# TC_board.net
KiCad netlist of a schematic drawn in EAGLE
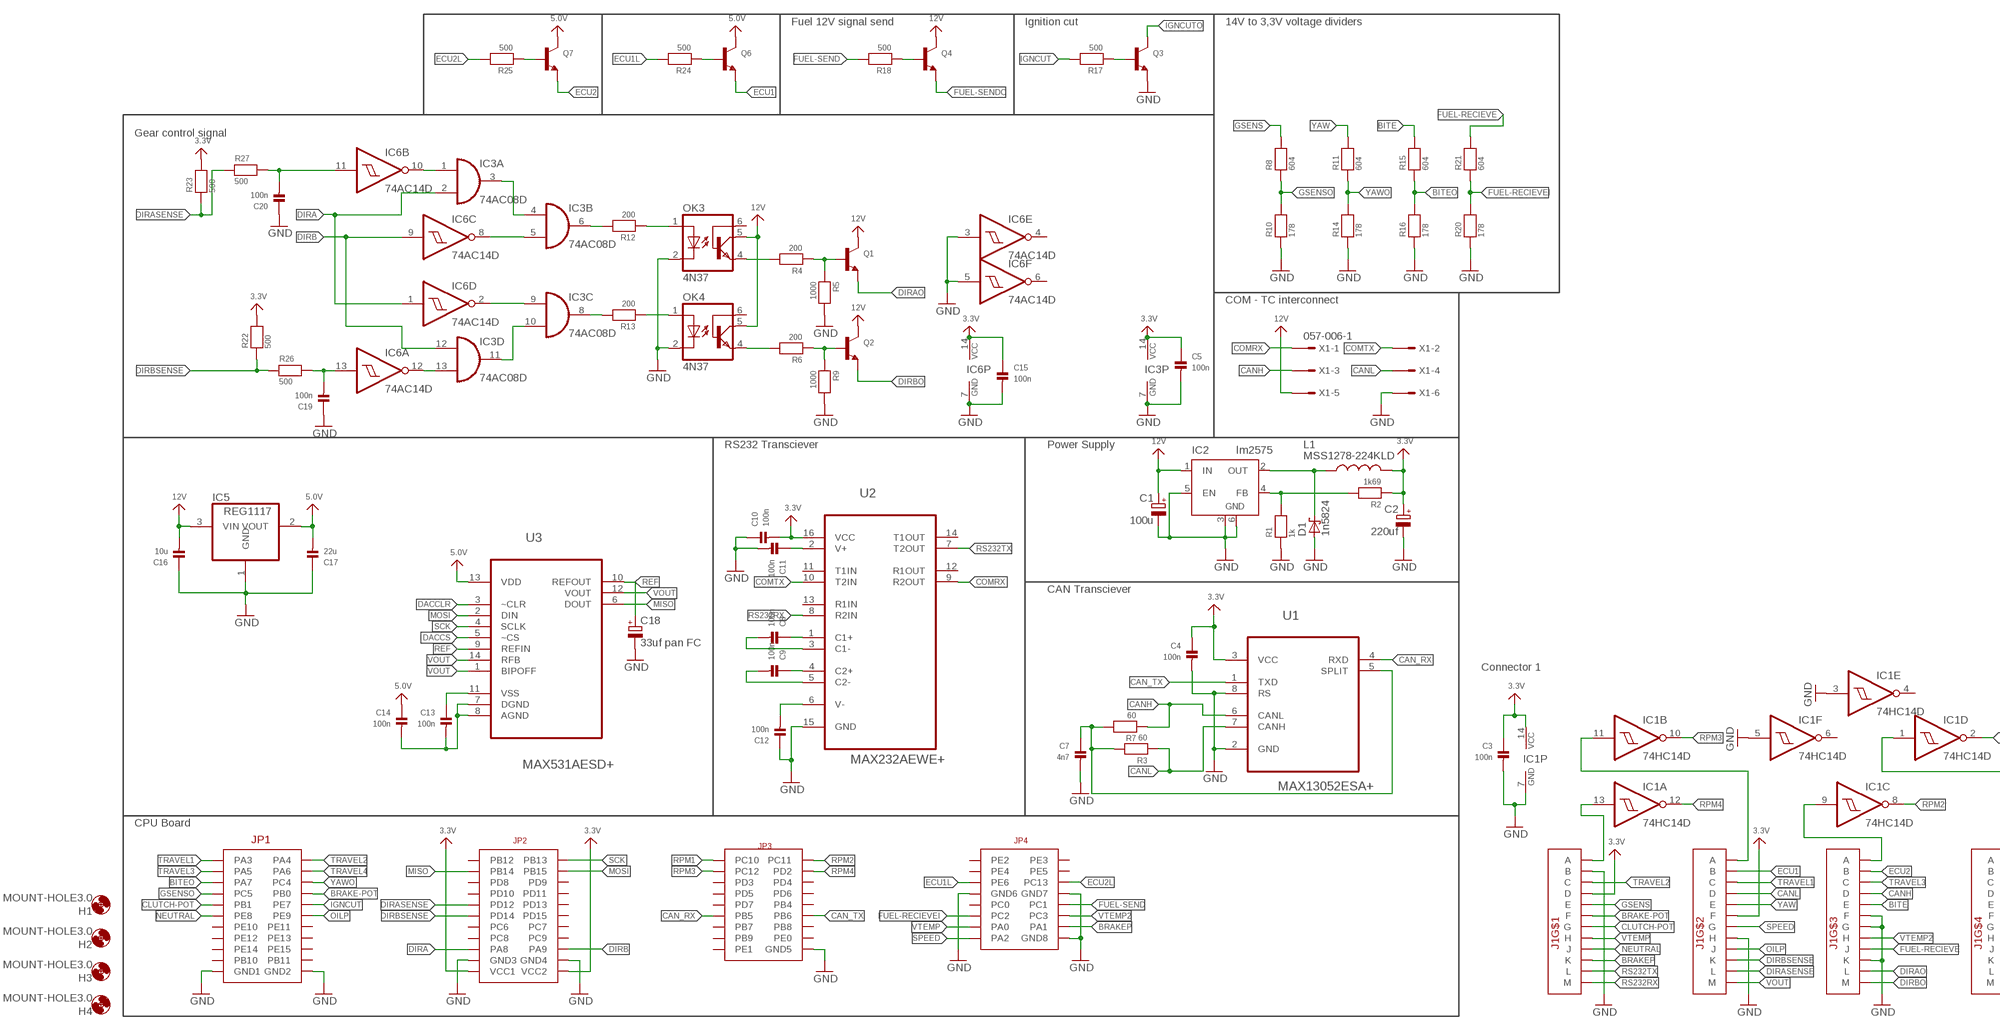
[diagram p0: schematic, sheet 1, part 1 of 2]
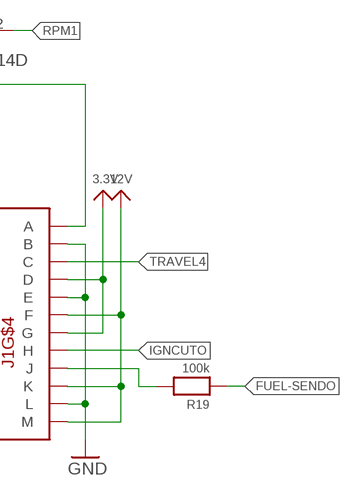
[diagram p1: schematic, sheet 1, part 2 of 2]

(export (version "E")
  (design (tool "Eeschema 10.0.6"))
  (components
    (comp (ref "C1")
      (value "100u")
      (footprint "eagle-import:E2,5-7")
      (libsource (lib "eagle-import") (part "CPOL-EUE2.5-7"))
    )
    (comp (ref "C2")
      (value "220uf")
      (footprint "eagle-import:E3,5-8")
      (libsource (lib "eagle-import") (part "CPOL-EUE3.5-8"))
    )
    (comp (ref "C3")
      (value "100n")
      (footprint "eagle-import:_0603")
      (libsource (lib "eagle-import") (part "CAP_CERAMIC_0603"))
    )
    (comp (ref "C4")
      (value "100n")
      (footprint "eagle-import:_0603")
      (libsource (lib "eagle-import") (part "CAP_CERAMIC_0603"))
    )
    (comp (ref "C5")
      (value "100n")
      (footprint "eagle-import:_0603")
      (libsource (lib "eagle-import") (part "CAP_CERAMIC_0603"))
    )
    (comp (ref "C7")
      (value "4n7")
      (footprint "eagle-import:_0603")
      (libsource (lib "eagle-import") (part "CAP_CERAMIC_0603"))
    )
    (comp (ref "C8")
      (value "100n")
      (footprint "eagle-import:_0603")
      (libsource (lib "eagle-import") (part "CAP_CERAMIC_0603"))
    )
    (comp (ref "C9")
      (value "100n")
      (footprint "eagle-import:_0603")
      (libsource (lib "eagle-import") (part "CAP_CERAMIC_0603"))
    )
    (comp (ref "C10")
      (value "100n")
      (footprint "eagle-import:_0603")
      (libsource (lib "eagle-import") (part "CAP_CERAMIC_0603"))
    )
    (comp (ref "C11")
      (value "100n")
      (footprint "eagle-import:_0603")
      (libsource (lib "eagle-import") (part "CAP_CERAMIC_0603"))
    )
    (comp (ref "C12")
      (value "100n")
      (footprint "eagle-import:_0603")
      (libsource (lib "eagle-import") (part "CAP_CERAMIC_0603"))
    )
    (comp (ref "C13")
      (value "100n")
      (footprint "eagle-import:_0603")
      (libsource (lib "eagle-import") (part "CAP_CERAMIC_0603"))
    )
    (comp (ref "C14")
      (value "100n")
      (footprint "eagle-import:_0603")
      (libsource (lib "eagle-import") (part "CAP_CERAMIC_0603"))
    )
    (comp (ref "C15")
      (value "100n")
      (footprint "eagle-import:_0603")
      (libsource (lib "eagle-import") (part "CAP_CERAMIC_0603"))
    )
    (comp (ref "C16")
      (value "10u")
      (footprint "eagle-import:_0805")
      (libsource (lib "eagle-import") (part "CAP_CERAMIC_0805"))
    )
    (comp (ref "C17")
      (value "22u")
      (footprint "eagle-import:_0805")
      (libsource (lib "eagle-import") (part "CAP_CERAMIC_0805"))
    )
    (comp (ref "C18")
      (value "33uf pan FC")
      (footprint "eagle-import:UD-5X5,8_NICHICON")
      (libsource (lib "eagle-import") (part "CPOL-EUUD-5X5,8"))
    )
    (comp (ref "C19")
      (value "100n")
      (footprint "eagle-import:_0805")
      (libsource (lib "eagle-import") (part "CAP_CERAMIC_0805"))
    )
    (comp (ref "C20")
      (value "100n")
      (footprint "eagle-import:_0805")
      (libsource (lib "eagle-import") (part "CAP_CERAMIC_0805"))
    )
    (comp (ref "D1")
      (value "1n5824")
      (footprint "eagle-import:F126Z12")
      (libsource (lib "eagle-import") (part "SCHOTTKY-DIODEF126Z12"))
    )
    (comp (ref "H1")
      (value "MOUNT-HOLE3.0")
      (footprint "eagle-import:3,0")
      (libsource (lib "eagle-import") (part "MOUNT-HOLE3.0"))
    )
    (comp (ref "H2")
      (value "MOUNT-HOLE3.0")
      (footprint "eagle-import:3,0")
      (libsource (lib "eagle-import") (part "MOUNT-HOLE3.0"))
    )
    (comp (ref "H3")
      (value "MOUNT-HOLE3.0")
      (footprint "eagle-import:3,0")
      (libsource (lib "eagle-import") (part "MOUNT-HOLE3.0"))
    )
    (comp (ref "H4")
      (value "MOUNT-HOLE3.0")
      (footprint "eagle-import:3,0")
      (libsource (lib "eagle-import") (part "MOUNT-HOLE3.0"))
    )
    (comp (ref "IC1")
      (value "74HC14D")
      (footprint "eagle-import:SO14")
      (libsource (lib "eagle-import") (part "7414DHC"))
    )
    (comp (ref "IC2")
      (value "lm2575")
      (footprint "eagle-import:TO263-5")
      (libsource (lib "eagle-import") (part "LM2596S"))
    )
    (comp (ref "IC3")
      (value "74AC08D")
      (footprint "eagle-import:SO14")
      (libsource (lib "eagle-import") (part "7408DAC"))
    )
    (comp (ref "IC5")
      (value "REG1117")
      (footprint "eagle-import:SOT223")
      (libsource (lib "eagle-import") (part "REG1117"))
    )
    (comp (ref "IC6")
      (value "74AC14D")
      (footprint "eagle-import:SO14")
      (libsource (lib "eagle-import") (part "7414DAC"))
    )
    (comp (ref "J1")
      (value "CON1")
      (footprint "eagle-import:AUTOCONNECTOR")
      (libsource (lib "eagle-import") (part "AUTOCONNECTOR"))
    )
    (comp (ref "L1")
      (value "MSS1278-224KLD")
      (footprint "eagle-import:CDRH125")
      (libsource (lib "eagle-import") (part "INDUCTORPWR"))
    )
    (comp (ref "OK3")
      (value "4N37")
      (footprint "eagle-import:DIL06")
      (fields (field (name "MF") "FAIRCHILD SEMICONDUCTOR"))
      (libsource (lib "eagle-import") (part "4N37"))
    )
    (comp (ref "OK4")
      (value "4N37")
      (footprint "eagle-import:DIL06")
      (fields (field (name "MF") "FAIRCHILD SEMICONDUCTOR"))
      (libsource (lib "eagle-import") (part "4N37"))
    )
    (comp (ref "Q1")
      (value "TRANSISTOR_NPNWIDE")
      (footprint "eagle-import:SOT23-WIDE")
      (libsource (lib "eagle-import") (part "TRANSISTOR_NPNWIDE"))
    )
    (comp (ref "Q2")
      (value "TRANSISTOR_NPNWIDE")
      (footprint "eagle-import:SOT23-WIDE")
      (libsource (lib "eagle-import") (part "TRANSISTOR_NPNWIDE"))
    )
    (comp (ref "Q3")
      (value "TRANSISTOR_NPNWIDE")
      (footprint "eagle-import:SOT23-WIDE")
      (libsource (lib "eagle-import") (part "TRANSISTOR_NPNWIDE"))
    )
    (comp (ref "Q4")
      (value "TRANSISTOR_NPNWIDE")
      (footprint "eagle-import:SOT23-WIDE")
      (libsource (lib "eagle-import") (part "TRANSISTOR_NPNWIDE"))
    )
    (comp (ref "Q6")
      (value "TRANSISTOR_NPNWIDE")
      (footprint "eagle-import:SOT23-WIDE")
      (libsource (lib "eagle-import") (part "TRANSISTOR_NPNWIDE"))
    )
    (comp (ref "Q7")
      (value "TRANSISTOR_NPNWIDE")
      (footprint "eagle-import:SOT23-WIDE")
      (libsource (lib "eagle-import") (part "TRANSISTOR_NPNWIDE"))
    )
    (comp (ref "R1")
      (value "1k")
      (footprint "eagle-import:_0603")
      (libsource (lib "eagle-import") (part "RESISTOR_0603"))
    )
    (comp (ref "R2")
      (value "1k69")
      (footprint "eagle-import:_0603")
      (libsource (lib "eagle-import") (part "RESISTOR_0603"))
    )
    (comp (ref "R3")
      (value "60")
      (footprint "eagle-import:_0603")
      (libsource (lib "eagle-import") (part "RESISTOR_0603"))
    )
    (comp (ref "R4")
      (value "200")
      (footprint "eagle-import:_0603")
      (libsource (lib "eagle-import") (part "RESISTOR_0603"))
    )
    (comp (ref "R5")
      (value "1000")
      (footprint "eagle-import:_0603")
      (libsource (lib "eagle-import") (part "RESISTOR_0603"))
    )
    (comp (ref "R6")
      (value "200")
      (footprint "eagle-import:_0603")
      (libsource (lib "eagle-import") (part "RESISTOR_0603"))
    )
    (comp (ref "R7")
      (value "60")
      (footprint "eagle-import:_0603")
      (libsource (lib "eagle-import") (part "RESISTOR_0603"))
    )
    (comp (ref "R8")
      (value "604")
      (footprint "eagle-import:_0603")
      (libsource (lib "eagle-import") (part "RESISTOR_0603"))
    )
    (comp (ref "R9")
      (value "1000")
      (footprint "eagle-import:_0603")
      (libsource (lib "eagle-import") (part "RESISTOR_0603"))
    )
    (comp (ref "R10")
      (value "178")
      (footprint "eagle-import:_0603")
      (libsource (lib "eagle-import") (part "RESISTOR_0603"))
    )
    (comp (ref "R11")
      (value "604")
      (footprint "eagle-import:_0603")
      (libsource (lib "eagle-import") (part "RESISTOR_0603"))
    )
    (comp (ref "R12")
      (value "200")
      (footprint "eagle-import:_0603")
      (libsource (lib "eagle-import") (part "RESISTOR_0603"))
    )
    (comp (ref "R13")
      (value "200")
      (footprint "eagle-import:_0603")
      (libsource (lib "eagle-import") (part "RESISTOR_0603"))
    )
    (comp (ref "R14")
      (value "178")
      (footprint "eagle-import:_0603")
      (libsource (lib "eagle-import") (part "RESISTOR_0603"))
    )
    (comp (ref "R15")
      (value "604")
      (footprint "eagle-import:_0603")
      (libsource (lib "eagle-import") (part "RESISTOR_0603"))
    )
    (comp (ref "R16")
      (value "178")
      (footprint "eagle-import:_0603")
      (libsource (lib "eagle-import") (part "RESISTOR_0603"))
    )
    (comp (ref "R17")
      (value "500")
      (footprint "eagle-import:_0603")
      (libsource (lib "eagle-import") (part "RESISTOR_0603"))
    )
    (comp (ref "R18")
      (value "500")
      (footprint "eagle-import:_0603")
      (libsource (lib "eagle-import") (part "RESISTOR_0603"))
    )
    (comp (ref "R19")
      (value "100k")
      (footprint "eagle-import:_0603")
      (libsource (lib "eagle-import") (part "RESISTOR_0603"))
    )
    (comp (ref "R20")
      (value "178")
      (footprint "eagle-import:_0603")
      (libsource (lib "eagle-import") (part "RESISTOR_0603"))
    )
    (comp (ref "R21")
      (value "604")
      (footprint "eagle-import:_0603")
      (libsource (lib "eagle-import") (part "RESISTOR_0603"))
    )
    (comp (ref "R22")
      (value "500")
      (footprint "eagle-import:_0603")
      (libsource (lib "eagle-import") (part "RESISTOR_0603"))
    )
    (comp (ref "R23")
      (value "500")
      (footprint "eagle-import:_0603")
      (libsource (lib "eagle-import") (part "RESISTOR_0603"))
    )
    (comp (ref "R24")
      (value "500")
      (footprint "eagle-import:_0603")
      (libsource (lib "eagle-import") (part "RESISTOR_0603"))
    )
    (comp (ref "R25")
      (value "500")
      (footprint "eagle-import:_0603")
      (libsource (lib "eagle-import") (part "RESISTOR_0603"))
    )
    (comp (ref "R26")
      (value "500")
      (footprint "eagle-import:_0603")
      (libsource (lib "eagle-import") (part "RESISTOR_0603"))
    )
    (comp (ref "R27")
      (value "500")
      (footprint "eagle-import:_0603")
      (libsource (lib "eagle-import") (part "RESISTOR_0603"))
    )
    (comp (ref "U$1")
      (value "CPU-BOARD")
      (footprint "eagle-import:CPU-BOARD-JP1")
      (libsource (lib "eagle-import") (part "CPU-BOARD"))
    )
    (comp (ref "U1")
      (value "MAX13052ESA+")
      (footprint "eagle-import:SOIC127P600X175-8N")
      (libsource (lib "eagle-import") (part "MAX13052ESA+"))
    )
    (comp (ref "U2")
      (value "MAX232AEWE+")
      (footprint "eagle-import:SOIC127P1032X265-16N")
      (libsource (lib "eagle-import") (part "MAX232AEWE+"))
    )
    (comp (ref "U3")
      (value "MAX531AESD+")
      (footprint "eagle-import:SOIC127P600X175-14N")
      (libsource (lib "eagle-import") (part "MAX531AESD+"))
    )
    (comp (ref "X1")
      (value "057-006-1")
      (footprint "eagle-import:057-006-1")
      (libsource (lib "eagle-import") (part "057-006-1"))
    )
  )
  (nets
    (net (code "1") (name "3.3V") (class "Default")
      (node (ref "C10") (pin "2") (pinfunction "P$2_2") (pintype "passive"))
      (node (ref "C15") (pin "1") (pinfunction "P$1_1") (pintype "passive"))
      (node (ref "C2") (pin "+") (pinfunction "+_+") (pintype "passive"))
      (node (ref "C3") (pin "1") (pinfunction "P$1_1") (pintype "passive"))
      (node (ref "C4") (pin "1") (pinfunction "P$1_1") (pintype "passive"))
      (node (ref "C5") (pin "1") (pinfunction "P$1_1") (pintype "passive"))
      (node (ref "IC1") (pin "14") (pinfunction "VCC_14") (pintype "power_in"))
      (node (ref "IC3") (pin "14") (pinfunction "VCC_14") (pintype "power_in"))
      (node (ref "IC6") (pin "14") (pinfunction "VCC_14") (pintype "power_in"))
      (node (ref "J1") (pin "D1") (pinfunction "D_D1") (pintype "bidirectional"))
      (node (ref "J1") (pin "D4") (pinfunction "D_D4") (pintype "bidirectional"))
      (node (ref "J1") (pin "F2") (pinfunction "F_F2") (pintype "bidirectional"))
      (node (ref "J1") (pin "G4") (pinfunction "G_G4") (pintype "bidirectional"))
      (node (ref "L1") (pin "2") (pinfunction "2_2") (pintype "passive"))
      (node (ref "R2") (pin "1") (pinfunction "1_1") (pintype "passive"))
      (node (ref "R22") (pin "2") (pinfunction "2_2") (pintype "passive"))
      (node (ref "R23") (pin "2") (pinfunction "2_2") (pintype "passive"))
      (node (ref "U$1") (pin "P$43") (pinfunction "VCC1_P$43") (pintype "bidirectional"))
      (node (ref "U$1") (pin "P$44") (pinfunction "VCC2_P$44") (pintype "bidirectional"))
      (node (ref "U1") (pin "3") (pinfunction "VCC_3") (pintype "power_in"))
      (node (ref "U2") (pin "16") (pinfunction "VCC_16") (pintype "power_in"))
    )
    (net (code "2") (name "5.0V") (class "Default")
      (node (ref "C14") (pin "1") (pinfunction "P$1_1") (pintype "passive"))
      (node (ref "C17") (pin "2") (pinfunction "P$2_2") (pintype "passive"))
      (node (ref "IC5") (pin "2") (pinfunction "VOUT_2") (pintype "output"))
      (node (ref "Q6") (pin "3") (pinfunction "C_3") (pintype "passive"))
      (node (ref "Q7") (pin "3") (pinfunction "C_3") (pintype "passive"))
      (node (ref "U3") (pin "13") (pinfunction "VDD_13") (pintype "power_in"))
    )
    (net (code "3") (name "12V") (class "Default")
      (node (ref "C1") (pin "+") (pinfunction "+_+") (pintype "passive"))
      (node (ref "C16") (pin "2") (pinfunction "P$2_2") (pintype "passive"))
      (node (ref "IC2") (pin "1") (pinfunction "IN_1") (pintype "input"))
      (node (ref "IC5") (pin "3") (pinfunction "VIN_3") (pintype "input"))
      (node (ref "J1") (pin "F4") (pinfunction "F_F4") (pintype "bidirectional"))
      (node (ref "J1") (pin "K4") (pinfunction "K_K4") (pintype "bidirectional"))
      (node (ref "J1") (pin "M4") (pinfunction "M_M4") (pintype "bidirectional"))
      (node (ref "OK3") (pin "5") (pinfunction "COL_5") (pintype "passive"))
      (node (ref "OK4") (pin "5") (pinfunction "COL_5") (pintype "passive"))
      (node (ref "Q1") (pin "3") (pinfunction "C_3") (pintype "passive"))
      (node (ref "Q2") (pin "3") (pinfunction "C_3") (pintype "passive"))
      (node (ref "Q4") (pin "3") (pinfunction "C_3") (pintype "passive"))
      (node (ref "X1") (pin "5") (pinfunction "S_5") (pintype "passive"))
    )
    (net (code "4") (name "BITE") (class "Default")
      (node (ref "J1") (pin "E3") (pinfunction "E_E3") (pintype "bidirectional"))
      (node (ref "R15") (pin "2") (pinfunction "2_2") (pintype "passive"))
    )
    (net (code "5") (name "BITEO") (class "Default")
      (node (ref "R15") (pin "1") (pinfunction "1_1") (pintype "passive"))
      (node (ref "R16") (pin "2") (pinfunction "2_2") (pintype "passive"))
      (node (ref "U$1") (pin "P$5") (pinfunction "PA7_P$5") (pintype "bidirectional"))
    )
    (net (code "6") (name "BRAKE-POT") (class "Default")
      (node (ref "J1") (pin "F1") (pinfunction "F_F1") (pintype "bidirectional"))
      (node (ref "U$1") (pin "P$8") (pinfunction "PB0_P$8") (pintype "bidirectional"))
    )
    (net (code "7") (name "BRAKEP") (class "Default")
      (node (ref "J1") (pin "K1") (pinfunction "K_K1") (pintype "bidirectional"))
      (node (ref "U$1") (pin "P$76") (pinfunction "PA1_P$76") (pintype "bidirectional"))
    )
    (net (code "8") (name "CANH") (class "Default")
      (node (ref "J1") (pin "D3") (pinfunction "D_D3") (pintype "bidirectional"))
      (node (ref "R7") (pin "1") (pinfunction "1_1") (pintype "passive"))
      (node (ref "U1") (pin "6") (pinfunction "CANL_6") (pintype "input"))
      (node (ref "X1") (pin "3") (pinfunction "S_3") (pintype "passive"))
    )
    (net (code "9") (name "CANL") (class "Default")
      (node (ref "J1") (pin "D2") (pinfunction "D_D2") (pintype "bidirectional"))
      (node (ref "R3") (pin "1") (pinfunction "1_1") (pintype "passive"))
      (node (ref "U1") (pin "7") (pinfunction "CANH_7") (pintype "input"))
      (node (ref "X1") (pin "4") (pinfunction "S_4") (pintype "passive"))
    )
    (net (code "10") (name "CAN_RX") (class "Default")
      (node (ref "U$1") (pin "P$55") (pinfunction "PB5_P$55") (pintype "bidirectional"))
      (node (ref "U1") (pin "4") (pinfunction "RXD_4") (pintype "output"))
    )
    (net (code "11") (name "CAN_TX") (class "Default")
      (node (ref "U$1") (pin "P$56") (pinfunction "PB6_P$56") (pintype "bidirectional"))
      (node (ref "U1") (pin "1") (pinfunction "TXD_1") (pintype "input"))
    )
    (net (code "12") (name "CLUTCH-POT") (class "Default")
      (node (ref "J1") (pin "G1") (pinfunction "G_G1") (pintype "bidirectional"))
      (node (ref "U$1") (pin "P$9") (pinfunction "PB1_P$9") (pintype "bidirectional"))
    )
    (net (code "13") (name "COMRX") (class "Default")
      (node (ref "U2") (pin "9") (pinfunction "R2OUT_9") (pintype "output"))
      (node (ref "X1") (pin "1") (pinfunction "S_1") (pintype "passive"))
    )
    (net (code "14") (name "COMTX") (class "Default")
      (node (ref "U2") (pin "10") (pinfunction "T2IN_10") (pintype "input"))
      (node (ref "X1") (pin "2") (pinfunction "S_2") (pintype "passive"))
    )
    (net (code "15") (name "DACCLR") (class "Default")
      (node (ref "U3") (pin "3") (pinfunction "~{CLR}_3") (pintype "input"))
    )
    (net (code "16") (name "DACCS") (class "Default")
      (node (ref "U3") (pin "5") (pinfunction "~{CS}_5") (pintype "input"))
    )
    (net (code "17") (name "DIRA") (class "Default")
      (node (ref "IC3") (pin "2") (pinfunction "I1_2") (pintype "input"))
      (node (ref "IC6") (pin "1") (pinfunction "I_1") (pintype "input"))
      (node (ref "U$1") (pin "P$39") (pinfunction "PA8_P$39") (pintype "bidirectional"))
    )
    (net (code "18") (name "DIRAO") (class "Default")
      (node (ref "J1") (pin "L3") (pinfunction "L_L3") (pintype "bidirectional"))
      (node (ref "Q1") (pin "2") (pinfunction "E_2") (pintype "passive"))
    )
    (net (code "19") (name "DIRASENSE") (class "Default")
      (node (ref "J1") (pin "L2") (pinfunction "L_L2") (pintype "bidirectional"))
      (node (ref "R23") (pin "1") (pinfunction "1_1") (pintype "passive"))
      (node (ref "R27") (pin "1") (pinfunction "1_1") (pintype "passive"))
      (node (ref "U$1") (pin "P$31") (pinfunction "PD12_P$31") (pintype "bidirectional"))
    )
    (net (code "20") (name "DIRB") (class "Default")
      (node (ref "IC3") (pin "12") (pinfunction "I0_12") (pintype "input"))
      (node (ref "IC6") (pin "9") (pinfunction "I_9") (pintype "input"))
      (node (ref "U$1") (pin "P$40") (pinfunction "PA9_P$40") (pintype "bidirectional"))
    )
    (net (code "21") (name "DIRBO") (class "Default")
      (node (ref "J1") (pin "M3") (pinfunction "M_M3") (pintype "bidirectional"))
      (node (ref "Q2") (pin "2") (pinfunction "E_2") (pintype "passive"))
    )
    (net (code "22") (name "DIRBSENSE") (class "Default")
      (node (ref "J1") (pin "K2") (pinfunction "K_K2") (pintype "bidirectional"))
      (node (ref "R22") (pin "1") (pinfunction "1_1") (pintype "passive"))
      (node (ref "R26") (pin "1") (pinfunction "1_1") (pintype "passive"))
      (node (ref "U$1") (pin "P$33") (pinfunction "PD14_P$33") (pintype "bidirectional"))
    )
    (net (code "23") (name "ECU1") (class "Default")
      (node (ref "J1") (pin "B2") (pinfunction "B_B2") (pintype "bidirectional"))
      (node (ref "Q6") (pin "2") (pinfunction "E_2") (pintype "passive"))
    )
    (net (code "24") (name "ECU1L") (class "Default")
      (node (ref "R24") (pin "2") (pinfunction "2_2") (pintype "passive"))
      (node (ref "U$1") (pin "P$67") (pinfunction "PE6_P$67") (pintype "bidirectional"))
    )
    (net (code "25") (name "ECU2") (class "Default")
      (node (ref "J1") (pin "B3") (pinfunction "B_B3") (pintype "bidirectional"))
      (node (ref "Q7") (pin "2") (pinfunction "E_2") (pintype "passive"))
    )
    (net (code "26") (name "ECU2L") (class "Default")
      (node (ref "R25") (pin "2") (pinfunction "2_2") (pintype "passive"))
      (node (ref "U$1") (pin "P$68") (pinfunction "PC13_P$68") (pintype "bidirectional"))
    )
    (net (code "27") (name "FUEL-RECIEVE") (class "Default")
      (node (ref "J1") (pin "J3") (pinfunction "J_J3") (pintype "bidirectional"))
      (node (ref "R21") (pin "2") (pinfunction "2_2") (pintype "passive"))
    )
    (net (code "28") (name "FUEL-RECIEVEI") (class "Default")
      (node (ref "R20") (pin "2") (pinfunction "2_2") (pintype "passive"))
      (node (ref "R21") (pin "1") (pinfunction "1_1") (pintype "passive"))
      (node (ref "U$1") (pin "P$73") (pinfunction "PC2_P$73") (pintype "bidirectional"))
    )
    (net (code "29") (name "FUEL-SEND") (class "Default")
      (node (ref "R18") (pin "2") (pinfunction "2_2") (pintype "passive"))
      (node (ref "U$1") (pin "P$72") (pinfunction "PC1_P$72") (pintype "bidirectional"))
    )
    (net (code "30") (name "FUEL-SENDO") (class "Default")
      (node (ref "Q4") (pin "2") (pinfunction "E_2") (pintype "passive"))
      (node (ref "R19") (pin "1") (pinfunction "1_1") (pintype "passive"))
    )
    (net (code "31") (name "GND") (class "Default")
      (node (ref "C1") (pin "-") (pinfunction "-_-") (pintype "passive"))
      (node (ref "C10") (pin "1") (pinfunction "P$1_1") (pintype "passive"))
      (node (ref "C11") (pin "2") (pinfunction "P$2_2") (pintype "passive"))
      (node (ref "C12") (pin "1") (pinfunction "P$1_1") (pintype "passive"))
      (node (ref "C15") (pin "2") (pinfunction "P$2_2") (pintype "passive"))
      (node (ref "C16") (pin "1") (pinfunction "P$1_1") (pintype "passive"))
      (node (ref "C17") (pin "1") (pinfunction "P$1_1") (pintype "passive"))
      (node (ref "C18") (pin "-") (pinfunction "-_-") (pintype "passive"))
      (node (ref "C19") (pin "1") (pinfunction "P$1_1") (pintype "passive"))
      (node (ref "C2") (pin "-") (pinfunction "-_-") (pintype "passive"))
      (node (ref "C20") (pin "1") (pinfunction "P$1_1") (pintype "passive"))
      (node (ref "C3") (pin "2") (pinfunction "P$2_2") (pintype "passive"))
      (node (ref "C4") (pin "2") (pinfunction "P$2_2") (pintype "passive"))
      (node (ref "C5") (pin "2") (pinfunction "P$2_2") (pintype "passive"))
      (node (ref "C7") (pin "2") (pinfunction "P$2_2") (pintype "passive"))
      (node (ref "D1") (pin "A") (pinfunction "A_A") (pintype "passive"))
      (node (ref "IC1") (pin "3") (pinfunction "I_3") (pintype "input"))
      (node (ref "IC1") (pin "5") (pinfunction "I_5") (pintype "input"))
      (node (ref "IC1") (pin "7") (pinfunction "GND_7") (pintype "power_in"))
      (node (ref "IC2") (pin "3") (pinfunction "GND_3") (pintype "power_in"))
      (node (ref "IC2") (pin "5") (pinfunction "EN_5") (pintype "input"))
      (node (ref "IC2") (pin "6") (pinfunction "GND_6") (pintype "power_in"))
      (node (ref "IC3") (pin "7") (pinfunction "GND_7") (pintype "power_in"))
      (node (ref "IC5") (pin "1") (pinfunction "GND_1") (pintype "power_in"))
      (node (ref "IC6") (pin "3") (pinfunction "I_3") (pintype "input"))
      (node (ref "IC6") (pin "5") (pinfunction "I_5") (pintype "input"))
      (node (ref "IC6") (pin "7") (pinfunction "GND_7") (pintype "power_in"))
      (node (ref "J1") (pin "B1") (pinfunction "B_B1") (pintype "bidirectional"))
      (node (ref "J1") (pin "B4") (pinfunction "B_B4") (pintype "bidirectional"))
      (node (ref "J1") (pin "E4") (pinfunction "E_E4") (pintype "bidirectional"))
      (node (ref "J1") (pin "F3") (pinfunction "F_F3") (pintype "bidirectional"))
      (node (ref "J1") (pin "G3") (pinfunction "G_G3") (pintype "bidirectional"))
      (node (ref "J1") (pin "H2") (pinfunction "H_H2") (pintype "bidirectional"))
      (node (ref "J1") (pin "K3") (pinfunction "K_K3") (pintype "bidirectional"))
      (node (ref "J1") (pin "L4") (pinfunction "L_L4") (pintype "bidirectional"))
      (node (ref "OK3") (pin "2") (pinfunction "C_2") (pintype "passive"))
      (node (ref "OK4") (pin "2") (pinfunction "C_2") (pintype "passive"))
      (node (ref "Q3") (pin "2") (pinfunction "E_2") (pintype "passive"))
      (node (ref "R1") (pin "1") (pinfunction "1_1") (pintype "passive"))
      (node (ref "R10") (pin "1") (pinfunction "1_1") (pintype "passive"))
      (node (ref "R14") (pin "1") (pinfunction "1_1") (pintype "passive"))
      (node (ref "R16") (pin "1") (pinfunction "1_1") (pintype "passive"))
      (node (ref "R20") (pin "1") (pinfunction "1_1") (pintype "passive"))
      (node (ref "R5") (pin "2") (pinfunction "2_2") (pintype "passive"))
      (node (ref "R9") (pin "2") (pinfunction "2_2") (pintype "passive"))
      (node (ref "U$1") (pin "P$19") (pinfunction "GND1_P$19") (pintype "bidirectional"))
      (node (ref "U$1") (pin "P$20") (pinfunction "GND2_P$20") (pintype "bidirectional"))
      (node (ref "U$1") (pin "P$41") (pinfunction "GND3_P$41") (pintype "bidirectional"))
      (node (ref "U$1") (pin "P$42") (pinfunction "GND4_P$42") (pintype "bidirectional"))
      (node (ref "U$1") (pin "P$62") (pinfunction "GND5_P$62") (pintype "bidirectional"))
      (node (ref "U$1") (pin "P$69") (pinfunction "GND6_P$69") (pintype "bidirectional"))
      (node (ref "U$1") (pin "P$70") (pinfunction "GND7_P$70") (pintype "bidirectional"))
      (node (ref "U$1") (pin "P$78") (pinfunction "GND8_P$78") (pintype "bidirectional"))
      (node (ref "U1") (pin "2") (pinfunction "GND_2") (pintype "passive"))
      (node (ref "U1") (pin "8") (pinfunction "RS_8") (pintype "input"))
      (node (ref "U2") (pin "15") (pinfunction "GND_15") (pintype "passive"))
      (node (ref "X1") (pin "6") (pinfunction "S_6") (pintype "passive"))
    )
    (net (code "32") (name "GSENS") (class "Default")
      (node (ref "J1") (pin "E1") (pinfunction "E_E1") (pintype "bidirectional"))
      (node (ref "R8") (pin "2") (pinfunction "2_2") (pintype "passive"))
    )
    (net (code "33") (name "GSENSO") (class "Default")
      (node (ref "R10") (pin "2") (pinfunction "2_2") (pintype "passive"))
      (node (ref "R8") (pin "1") (pinfunction "1_1") (pintype "passive"))
      (node (ref "U$1") (pin "P$7") (pinfunction "PC5_P$7") (pintype "bidirectional"))
    )
    (net (code "34") (name "IGNCUT") (class "Default")
      (node (ref "R17") (pin "2") (pinfunction "2_2") (pintype "passive"))
      (node (ref "U$1") (pin "P$10") (pinfunction "PE7_P$10") (pintype "bidirectional"))
    )
    (net (code "35") (name "IGNCUTO") (class "Default")
      (node (ref "J1") (pin "H4") (pinfunction "H_H4") (pintype "bidirectional"))
      (node (ref "Q3") (pin "3") (pinfunction "C_3") (pintype "passive"))
    )
    (net (code "36") (name "MISO") (class "Default")
      (node (ref "U$1") (pin "P$25") (pinfunction "PB14_P$25") (pintype "bidirectional"))
      (node (ref "U3") (pin "6") (pinfunction "DOUT_6") (pintype "output"))
    )
    (net (code "37") (name "MOSI") (class "Default")
      (node (ref "U$1") (pin "P$26") (pinfunction "PB15_P$26") (pintype "bidirectional"))
      (node (ref "U3") (pin "2") (pinfunction "DIN_2") (pintype "input"))
    )
    (net (code "38") (name "NEUTRAL") (class "Default")
      (node (ref "J1") (pin "J1") (pinfunction "J_J1") (pintype "bidirectional"))
      (node (ref "U$1") (pin "P$11") (pinfunction "PE8_P$11") (pintype "bidirectional"))
    )
    (net (code "39") (name "Net-(C7-P$1)") (class "Default")
      (node (ref "C7") (pin "1") (pinfunction "P$1_1") (pintype "passive"))
      (node (ref "R3") (pin "2") (pinfunction "2_2") (pintype "passive"))
      (node (ref "R7") (pin "2") (pinfunction "2_2") (pintype "passive"))
      (node (ref "U1") (pin "5") (pinfunction "SPLIT_5") (pintype "output"))
    )
    (net (code "40") (name "Net-(C8-P$1)") (class "Default")
      (node (ref "C8") (pin "1") (pinfunction "P$1_1") (pintype "passive"))
      (node (ref "U2") (pin "1") (pinfunction "C1+_1") (pintype "input"))
    )
    (net (code "41") (name "Net-(C8-P$2)") (class "Default")
      (node (ref "C8") (pin "2") (pinfunction "P$2_2") (pintype "passive"))
      (node (ref "U2") (pin "3") (pinfunction "C1-_3") (pintype "input"))
    )
    (net (code "42") (name "Net-(C9-P$1)") (class "Default")
      (node (ref "C9") (pin "1") (pinfunction "P$1_1") (pintype "passive"))
      (node (ref "U2") (pin "4") (pinfunction "C2+_4") (pintype "input"))
    )
    (net (code "43") (name "Net-(C9-P$2)") (class "Default")
      (node (ref "C9") (pin "2") (pinfunction "P$2_2") (pintype "passive"))
      (node (ref "U2") (pin "5") (pinfunction "C2-_5") (pintype "input"))
    )
    (net (code "44") (name "Net-(C11-P$1)") (class "Default")
      (node (ref "C11") (pin "1") (pinfunction "P$1_1") (pintype "passive"))
      (node (ref "U2") (pin "2") (pinfunction "V+_2") (pintype "power_in"))
    )
    (net (code "45") (name "Net-(C12-P$2)") (class "Default")
      (node (ref "C12") (pin "2") (pinfunction "P$2_2") (pintype "passive"))
      (node (ref "U2") (pin "6") (pinfunction "V-_6") (pintype "power_in"))
    )
    (net (code "46") (name "Net-(C13-P$1)") (class "Default")
      (node (ref "C13") (pin "1") (pinfunction "P$1_1") (pintype "passive"))
      (node (ref "U3") (pin "11") (pinfunction "VSS_11") (pintype "power_in"))
    )
    (net (code "47") (name "Net-(C13-P$2)") (class "Default")
      (node (ref "C13") (pin "2") (pinfunction "P$2_2") (pintype "passive"))
      (node (ref "C14") (pin "2") (pinfunction "P$2_2") (pintype "passive"))
      (node (ref "U3") (pin "7") (pinfunction "DGND_7") (pintype "passive"))
      (node (ref "U3") (pin "8") (pinfunction "AGND_8") (pintype "passive"))
    )
    (net (code "48") (name "Net-(C19-P$2)") (class "Default")
      (node (ref "C19") (pin "2") (pinfunction "P$2_2") (pintype "passive"))
      (node (ref "IC6") (pin "13") (pinfunction "I_13") (pintype "input"))
      (node (ref "R26") (pin "2") (pinfunction "2_2") (pintype "passive"))
    )
    (net (code "49") (name "Net-(C20-P$2)") (class "Default")
      (node (ref "C20") (pin "2") (pinfunction "P$2_2") (pintype "passive"))
      (node (ref "IC6") (pin "11") (pinfunction "I_11") (pintype "input"))
      (node (ref "R27") (pin "2") (pinfunction "2_2") (pintype "passive"))
    )
    (net (code "50") (name "Net-(IC1A-I)") (class "Default")
      (node (ref "IC1") (pin "13") (pinfunction "I_13") (pintype "input"))
      (node (ref "J1") (pin "A1") (pinfunction "A_A1") (pintype "bidirectional"))
    )
    (net (code "51") (name "Net-(IC1B-I)") (class "Default")
      (node (ref "IC1") (pin "11") (pinfunction "I_11") (pintype "input"))
      (node (ref "J1") (pin "A2") (pinfunction "A_A2") (pintype "bidirectional"))
    )
    (net (code "52") (name "Net-(IC1C-I)") (class "Default")
      (node (ref "IC1") (pin "9") (pinfunction "I_9") (pintype "input"))
      (node (ref "J1") (pin "A3") (pinfunction "A_A3") (pintype "bidirectional"))
    )
    (net (code "53") (name "Net-(IC1D-I)") (class "Default")
      (node (ref "IC1") (pin "1") (pinfunction "I_1") (pintype "input"))
      (node (ref "J1") (pin "A4") (pinfunction "A_A4") (pintype "bidirectional"))
    )
    (net (code "54") (name "Net-(IC2-FB)") (class "Default")
      (node (ref "IC2") (pin "4") (pinfunction "FB_4") (pintype "input"))
      (node (ref "R1") (pin "2") (pinfunction "2_2") (pintype "passive"))
      (node (ref "R2") (pin "2") (pinfunction "2_2") (pintype "passive"))
    )
    (net (code "55") (name "Net-(IC2-OUT)") (class "Default")
      (node (ref "D1") (pin "C") (pinfunction "C_C") (pintype "passive"))
      (node (ref "IC2") (pin "2") (pinfunction "OUT_2") (pintype "output"))
      (node (ref "L1") (pin "1") (pinfunction "1_1") (pintype "passive"))
    )
    (net (code "56") (name "Net-(IC3A-I0)") (class "Default")
      (node (ref "IC3") (pin "1") (pinfunction "I0_1") (pintype "input"))
      (node (ref "IC6") (pin "10") (pinfunction "O_10") (pintype "output"))
    )
    (net (code "57") (name "Net-(IC3A-O)") (class "Default")
      (node (ref "IC3") (pin "3") (pinfunction "O_3") (pintype "output"))
      (node (ref "IC3") (pin "4") (pinfunction "I0_4") (pintype "input"))
    )
    (net (code "58") (name "Net-(IC3B-I1)") (class "Default")
      (node (ref "IC3") (pin "5") (pinfunction "I1_5") (pintype "input"))
      (node (ref "IC6") (pin "8") (pinfunction "O_8") (pintype "output"))
    )
    (net (code "59") (name "Net-(IC3B-O)") (class "Default")
      (node (ref "IC3") (pin "6") (pinfunction "O_6") (pintype "output"))
      (node (ref "R12") (pin "2") (pinfunction "2_2") (pintype "passive"))
    )
    (net (code "60") (name "Net-(IC3C-I0)") (class "Default")
      (node (ref "IC3") (pin "9") (pinfunction "I0_9") (pintype "input"))
      (node (ref "IC6") (pin "2") (pinfunction "O_2") (pintype "output"))
    )
    (net (code "61") (name "Net-(IC3C-I1)") (class "Default")
      (node (ref "IC3") (pin "10") (pinfunction "I1_10") (pintype "input"))
      (node (ref "IC3") (pin "11") (pinfunction "O_11") (pintype "output"))
    )
    (net (code "62") (name "Net-(IC3C-O)") (class "Default")
      (node (ref "IC3") (pin "8") (pinfunction "O_8") (pintype "output"))
      (node (ref "R13") (pin "2") (pinfunction "2_2") (pintype "passive"))
    )
    (net (code "63") (name "Net-(IC3D-I1)") (class "Default")
      (node (ref "IC3") (pin "13") (pinfunction "I1_13") (pintype "input"))
      (node (ref "IC6") (pin "12") (pinfunction "O_12") (pintype "output"))
    )
    (net (code "64") (name "Net-(J1D-J)") (class "Default")
      (node (ref "J1") (pin "J4") (pinfunction "J_J4") (pintype "bidirectional"))
      (node (ref "R19") (pin "2") (pinfunction "2_2") (pintype "passive"))
    )
    (net (code "65") (name "Net-(OK3-A)") (class "Default")
      (node (ref "OK3") (pin "1") (pinfunction "A_1") (pintype "passive"))
      (node (ref "R12") (pin "1") (pinfunction "1_1") (pintype "passive"))
    )
    (net (code "66") (name "Net-(OK3-EMI)") (class "Default")
      (node (ref "OK3") (pin "4") (pinfunction "EMI_4") (pintype "passive"))
      (node (ref "R4") (pin "2") (pinfunction "2_2") (pintype "passive"))
    )
    (net (code "67") (name "Net-(OK4-A)") (class "Default")
      (node (ref "OK4") (pin "1") (pinfunction "A_1") (pintype "passive"))
      (node (ref "R13") (pin "1") (pinfunction "1_1") (pintype "passive"))
    )
    (net (code "68") (name "Net-(OK4-EMI)") (class "Default")
      (node (ref "OK4") (pin "4") (pinfunction "EMI_4") (pintype "passive"))
      (node (ref "R6") (pin "2") (pinfunction "2_2") (pintype "passive"))
    )
    (net (code "69") (name "Net-(Q1-B)") (class "Default")
      (node (ref "Q1") (pin "1") (pinfunction "B_1") (pintype "passive"))
      (node (ref "R4") (pin "1") (pinfunction "1_1") (pintype "passive"))
      (node (ref "R5") (pin "1") (pinfunction "1_1") (pintype "passive"))
    )
    (net (code "70") (name "Net-(Q2-B)") (class "Default")
      (node (ref "Q2") (pin "1") (pinfunction "B_1") (pintype "passive"))
      (node (ref "R6") (pin "1") (pinfunction "1_1") (pintype "passive"))
      (node (ref "R9") (pin "1") (pinfunction "1_1") (pintype "passive"))
    )
    (net (code "71") (name "Net-(Q3-B)") (class "Default")
      (node (ref "Q3") (pin "1") (pinfunction "B_1") (pintype "passive"))
      (node (ref "R17") (pin "1") (pinfunction "1_1") (pintype "passive"))
    )
    (net (code "72") (name "Net-(Q4-B)") (class "Default")
      (node (ref "Q4") (pin "1") (pinfunction "B_1") (pintype "passive"))
      (node (ref "R18") (pin "1") (pinfunction "1_1") (pintype "passive"))
    )
    (net (code "73") (name "Net-(Q6-B)") (class "Default")
      (node (ref "Q6") (pin "1") (pinfunction "B_1") (pintype "passive"))
      (node (ref "R24") (pin "1") (pinfunction "1_1") (pintype "passive"))
    )
    (net (code "74") (name "Net-(Q7-B)") (class "Default")
      (node (ref "Q7") (pin "1") (pinfunction "B_1") (pintype "passive"))
      (node (ref "R25") (pin "1") (pinfunction "1_1") (pintype "passive"))
    )
    (net (code "75") (name "OILP") (class "Default")
      (node (ref "J1") (pin "J2") (pinfunction "J_J2") (pintype "bidirectional"))
      (node (ref "U$1") (pin "P$12") (pinfunction "PE9_P$12") (pintype "bidirectional"))
    )
    (net (code "76") (name "REF") (class "Default")
      (node (ref "C18") (pin "+") (pinfunction "+_+") (pintype "passive"))
      (node (ref "U3") (pin "10") (pinfunction "REFOUT_10") (pintype "output"))
      (node (ref "U3") (pin "9") (pinfunction "REFIN_9") (pintype "input"))
    )
    (net (code "77") (name "RPM1") (class "Default")
      (node (ref "IC1") (pin "2") (pinfunction "O_2") (pintype "output"))
      (node (ref "U$1") (pin "P$45") (pinfunction "PC10_P$45") (pintype "bidirectional"))
    )
    (net (code "78") (name "RPM2") (class "Default")
      (node (ref "IC1") (pin "8") (pinfunction "O_8") (pintype "output"))
      (node (ref "U$1") (pin "P$46") (pinfunction "PC11_P$46") (pintype "bidirectional"))
    )
    (net (code "79") (name "RPM3") (class "Default")
      (node (ref "IC1") (pin "10") (pinfunction "O_10") (pintype "output"))
      (node (ref "U$1") (pin "P$47") (pinfunction "PC12_P$47") (pintype "bidirectional"))
    )
    (net (code "80") (name "RPM4") (class "Default")
      (node (ref "IC1") (pin "12") (pinfunction "O_12") (pintype "output"))
      (node (ref "U$1") (pin "P$48") (pinfunction "PD2_P$48") (pintype "bidirectional"))
    )
    (net (code "81") (name "RS232RX") (class "Default")
      (node (ref "J1") (pin "M1") (pinfunction "M_M1") (pintype "bidirectional"))
      (node (ref "U2") (pin "8") (pinfunction "R2IN_8") (pintype "input"))
    )
    (net (code "82") (name "RS232TX") (class "Default")
      (node (ref "J1") (pin "L1") (pinfunction "L_L1") (pintype "bidirectional"))
      (node (ref "U2") (pin "7") (pinfunction "T2OUT_7") (pintype "output"))
    )
    (net (code "83") (name "SCK") (class "Default")
      (node (ref "U$1") (pin "P$24") (pinfunction "PB13_P$24") (pintype "bidirectional"))
      (node (ref "U3") (pin "4") (pinfunction "SCLK_4") (pintype "input"))
    )
    (net (code "84") (name "SPEED") (class "Default")
      (node (ref "J1") (pin "G2") (pinfunction "G_G2") (pintype "bidirectional"))
      (node (ref "U$1") (pin "P$77") (pinfunction "PA2_P$77") (pintype "bidirectional"))
    )
    (net (code "85") (name "TRAVEL1") (class "Default")
      (node (ref "J1") (pin "C2") (pinfunction "C_C2") (pintype "bidirectional"))
      (node (ref "U$1") (pin "P$1") (pinfunction "PA3_P$1") (pintype "bidirectional"))
    )
    (net (code "86") (name "TRAVEL2") (class "Default")
      (node (ref "J1") (pin "C1") (pinfunction "C_C1") (pintype "bidirectional"))
      (node (ref "U$1") (pin "P$2") (pinfunction "PA4_P$2") (pintype "bidirectional"))
    )
    (net (code "87") (name "TRAVEL3") (class "Default")
      (node (ref "J1") (pin "C3") (pinfunction "C_C3") (pintype "bidirectional"))
      (node (ref "U$1") (pin "P$3") (pinfunction "PA5_P$3") (pintype "bidirectional"))
    )
    (net (code "88") (name "TRAVEL4") (class "Default")
      (node (ref "J1") (pin "C4") (pinfunction "C_C4") (pintype "bidirectional"))
      (node (ref "U$1") (pin "P$4") (pinfunction "PA6_P$4") (pintype "bidirectional"))
    )
    (net (code "89") (name "VOUT") (class "Default")
      (node (ref "J1") (pin "M2") (pinfunction "M_M2") (pintype "bidirectional"))
      (node (ref "U3") (pin "1") (pinfunction "BIPOFF_1") (pintype "passive"))
      (node (ref "U3") (pin "12") (pinfunction "VOUT_12") (pintype "output"))
      (node (ref "U3") (pin "14") (pinfunction "RFB_14") (pintype "passive"))
    )
    (net (code "90") (name "VTEMP") (class "Default")
      (node (ref "J1") (pin "H1") (pinfunction "H_H1") (pintype "bidirectional"))
      (node (ref "U$1") (pin "P$75") (pinfunction "PA0_P$75") (pintype "bidirectional"))
    )
    (net (code "91") (name "VTEMP2") (class "Default")
      (node (ref "J1") (pin "H3") (pinfunction "H_H3") (pintype "bidirectional"))
      (node (ref "U$1") (pin "P$74") (pinfunction "PC3_P$74") (pintype "bidirectional"))
    )
    (net (code "92") (name "YAW") (class "Default")
      (node (ref "J1") (pin "E2") (pinfunction "E_E2") (pintype "bidirectional"))
      (node (ref "R11") (pin "2") (pinfunction "2_2") (pintype "passive"))
    )
    (net (code "93") (name "YAWO") (class "Default")
      (node (ref "R11") (pin "1") (pinfunction "1_1") (pintype "passive"))
      (node (ref "R14") (pin "2") (pinfunction "2_2") (pintype "passive"))
      (node (ref "U$1") (pin "P$6") (pinfunction "PC4_P$6") (pintype "bidirectional"))
    )
    (net (code "94") (name "unconnected-(IC1E-O-Pad4)") (class "Default")
      (node (ref "IC1") (pin "4") (pinfunction "O_4") (pintype "output"))
    )
    (net (code "95") (name "unconnected-(IC1F-O-Pad6)") (class "Default")
      (node (ref "IC1") (pin "6") (pinfunction "O_6") (pintype "output"))
    )
    (net (code "96") (name "unconnected-(IC6E-O-Pad4)") (class "Default")
      (node (ref "IC6") (pin "4") (pinfunction "O_4") (pintype "output"))
    )
    (net (code "97") (name "unconnected-(IC6F-O-Pad6)") (class "Default")
      (node (ref "IC6") (pin "6") (pinfunction "O_6") (pintype "output"))
    )
    (net (code "98") (name "unconnected-(OK3-BAS-Pad6)") (class "Default")
      (node (ref "OK3") (pin "6") (pinfunction "BAS_6") (pintype "passive"))
    )
    (net (code "99") (name "unconnected-(OK4-BAS-Pad6)") (class "Default")
      (node (ref "OK4") (pin "6") (pinfunction "BAS_6") (pintype "passive"))
    )
    (net (code "100") (name "unconnected-(U$1A-PB10-PadP$21)") (class "Default")
      (node (ref "U$1") (pin "P$21") (pinfunction "PB10_P$21") (pintype "bidirectional"))
    )
    (net (code "101") (name "unconnected-(U$1A-PB11-PadP$22)") (class "Default")
      (node (ref "U$1") (pin "P$22") (pinfunction "PB11_P$22") (pintype "bidirectional"))
    )
    (net (code "102") (name "unconnected-(U$1A-PE10-PadP$13)") (class "Default")
      (node (ref "U$1") (pin "P$13") (pinfunction "PE10_P$13") (pintype "bidirectional"))
    )
    (net (code "103") (name "unconnected-(U$1A-PE11-PadP$14)") (class "Default")
      (node (ref "U$1") (pin "P$14") (pinfunction "PE11_P$14") (pintype "bidirectional"))
    )
    (net (code "104") (name "unconnected-(U$1A-PE12-PadP$15)") (class "Default")
      (node (ref "U$1") (pin "P$15") (pinfunction "PE12_P$15") (pintype "bidirectional"))
    )
    (net (code "105") (name "unconnected-(U$1A-PE13-PadP$16)") (class "Default")
      (node (ref "U$1") (pin "P$16") (pinfunction "PE13_P$16") (pintype "bidirectional"))
    )
    (net (code "106") (name "unconnected-(U$1A-PE14-PadP$17)") (class "Default")
      (node (ref "U$1") (pin "P$17") (pinfunction "PE14_P$17") (pintype "bidirectional"))
    )
    (net (code "107") (name "unconnected-(U$1A-PE15-PadP$18)") (class "Default")
      (node (ref "U$1") (pin "P$18") (pinfunction "PE15_P$18") (pintype "bidirectional"))
    )
    (net (code "108") (name "unconnected-(U$1B-PB12-PadP$23)") (class "Default")
      (node (ref "U$1") (pin "P$23") (pinfunction "PB12_P$23") (pintype "bidirectional"))
    )
    (net (code "109") (name "unconnected-(U$1B-PC6-PadP$35)") (class "Default")
      (node (ref "U$1") (pin "P$35") (pinfunction "PC6_P$35") (pintype "bidirectional"))
    )
    (net (code "110") (name "unconnected-(U$1B-PC7-PadP$36)") (class "Default")
      (node (ref "U$1") (pin "P$36") (pinfunction "PC7_P$36") (pintype "bidirectional"))
    )
    (net (code "111") (name "unconnected-(U$1B-PC8-PadP$37)") (class "Default")
      (node (ref "U$1") (pin "P$37") (pinfunction "PC8_P$37") (pintype "bidirectional"))
    )
    (net (code "112") (name "unconnected-(U$1B-PC9-PadP$38)") (class "Default")
      (node (ref "U$1") (pin "P$38") (pinfunction "PC9_P$38") (pintype "bidirectional"))
    )
    (net (code "113") (name "unconnected-(U$1B-PD8-PadP$27)") (class "Default")
      (node (ref "U$1") (pin "P$27") (pinfunction "PD8_P$27") (pintype "bidirectional"))
    )
    (net (code "114") (name "unconnected-(U$1B-PD9-PadP$28)") (class "Default")
      (node (ref "U$1") (pin "P$28") (pinfunction "PD9_P$28") (pintype "bidirectional"))
    )
    (net (code "115") (name "unconnected-(U$1B-PD10-PadP$29)") (class "Default")
      (node (ref "U$1") (pin "P$29") (pinfunction "PD10_P$29") (pintype "bidirectional"))
    )
    (net (code "116") (name "unconnected-(U$1B-PD11-PadP$30)") (class "Default")
      (node (ref "U$1") (pin "P$30") (pinfunction "PD11_P$30") (pintype "bidirectional"))
    )
    (net (code "117") (name "unconnected-(U$1B-PD13-PadP$32)") (class "Default")
      (node (ref "U$1") (pin "P$32") (pinfunction "PD13_P$32") (pintype "bidirectional"))
    )
    (net (code "118") (name "unconnected-(U$1B-PD15-PadP$34)") (class "Default")
      (node (ref "U$1") (pin "P$34") (pinfunction "PD15_P$34") (pintype "bidirectional"))
    )
    (net (code "119") (name "unconnected-(U$1C-PB4-PadP$54)") (class "Default")
      (node (ref "U$1") (pin "P$54") (pinfunction "PB4_P$54") (pintype "bidirectional"))
    )
    (net (code "120") (name "unconnected-(U$1C-PB7-PadP$57)") (class "Default")
      (node (ref "U$1") (pin "P$57") (pinfunction "PB7_P$57") (pintype "bidirectional"))
    )
    (net (code "121") (name "unconnected-(U$1C-PB8-PadP$58)") (class "Default")
      (node (ref "U$1") (pin "P$58") (pinfunction "PB8_P$58") (pintype "bidirectional"))
    )
    (net (code "122") (name "unconnected-(U$1C-PB9-PadP$59)") (class "Default")
      (node (ref "U$1") (pin "P$59") (pinfunction "PB9_P$59") (pintype "bidirectional"))
    )
    (net (code "123") (name "unconnected-(U$1C-PD3-PadP$49)") (class "Default")
      (node (ref "U$1") (pin "P$49") (pinfunction "PD3_P$49") (pintype "bidirectional"))
    )
    (net (code "124") (name "unconnected-(U$1C-PD4-PadP$50)") (class "Default")
      (node (ref "U$1") (pin "P$50") (pinfunction "PD4_P$50") (pintype "bidirectional"))
    )
    (net (code "125") (name "unconnected-(U$1C-PD5-PadP$51)") (class "Default")
      (node (ref "U$1") (pin "P$51") (pinfunction "PD5_P$51") (pintype "bidirectional"))
    )
    (net (code "126") (name "unconnected-(U$1C-PD6-PadP$52)") (class "Default")
      (node (ref "U$1") (pin "P$52") (pinfunction "PD6_P$52") (pintype "bidirectional"))
    )
    (net (code "127") (name "unconnected-(U$1C-PD7-PadP$53)") (class "Default")
      (node (ref "U$1") (pin "P$53") (pinfunction "PD7_P$53") (pintype "bidirectional"))
    )
    (net (code "128") (name "unconnected-(U$1C-PE0-PadP$60)") (class "Default")
      (node (ref "U$1") (pin "P$60") (pinfunction "PE0_P$60") (pintype "bidirectional"))
    )
    (net (code "129") (name "unconnected-(U$1C-PE1-PadP$61)") (class "Default")
      (node (ref "U$1") (pin "P$61") (pinfunction "PE1_P$61") (pintype "bidirectional"))
    )
    (net (code "130") (name "unconnected-(U$1D-PC0-PadP$71)") (class "Default")
      (node (ref "U$1") (pin "P$71") (pinfunction "PC0_P$71") (pintype "bidirectional"))
    )
    (net (code "131") (name "unconnected-(U$1D-PE2-PadP$63)") (class "Default")
      (node (ref "U$1") (pin "P$63") (pinfunction "PE2_P$63") (pintype "bidirectional"))
    )
    (net (code "132") (name "unconnected-(U$1D-PE3-PadP$64)") (class "Default")
      (node (ref "U$1") (pin "P$64") (pinfunction "PE3_P$64") (pintype "bidirectional"))
    )
    (net (code "133") (name "unconnected-(U$1D-PE4-PadP$65)") (class "Default")
      (node (ref "U$1") (pin "P$65") (pinfunction "PE4_P$65") (pintype "bidirectional"))
    )
    (net (code "134") (name "unconnected-(U$1D-PE5-PadP$66)") (class "Default")
      (node (ref "U$1") (pin "P$66") (pinfunction "PE5_P$66") (pintype "bidirectional"))
    )
    (net (code "135") (name "unconnected-(U2-R1IN-Pad13)") (class "Default")
      (node (ref "U2") (pin "13") (pinfunction "R1IN_13") (pintype "input"))
    )
    (net (code "136") (name "unconnected-(U2-R1OUT-Pad12)") (class "Default")
      (node (ref "U2") (pin "12") (pinfunction "R1OUT_12") (pintype "output"))
    )
    (net (code "137") (name "unconnected-(U2-T1IN-Pad11)") (class "Default")
      (node (ref "U2") (pin "11") (pinfunction "T1IN_11") (pintype "input"))
    )
    (net (code "138") (name "unconnected-(U2-T1OUT-Pad14)") (class "Default")
      (node (ref "U2") (pin "14") (pinfunction "T1OUT_14") (pintype "output"))
    )
  )
)
